# LT3045_and_LT3094.net
KiCad netlist of a schematic drawn in Altium Designer
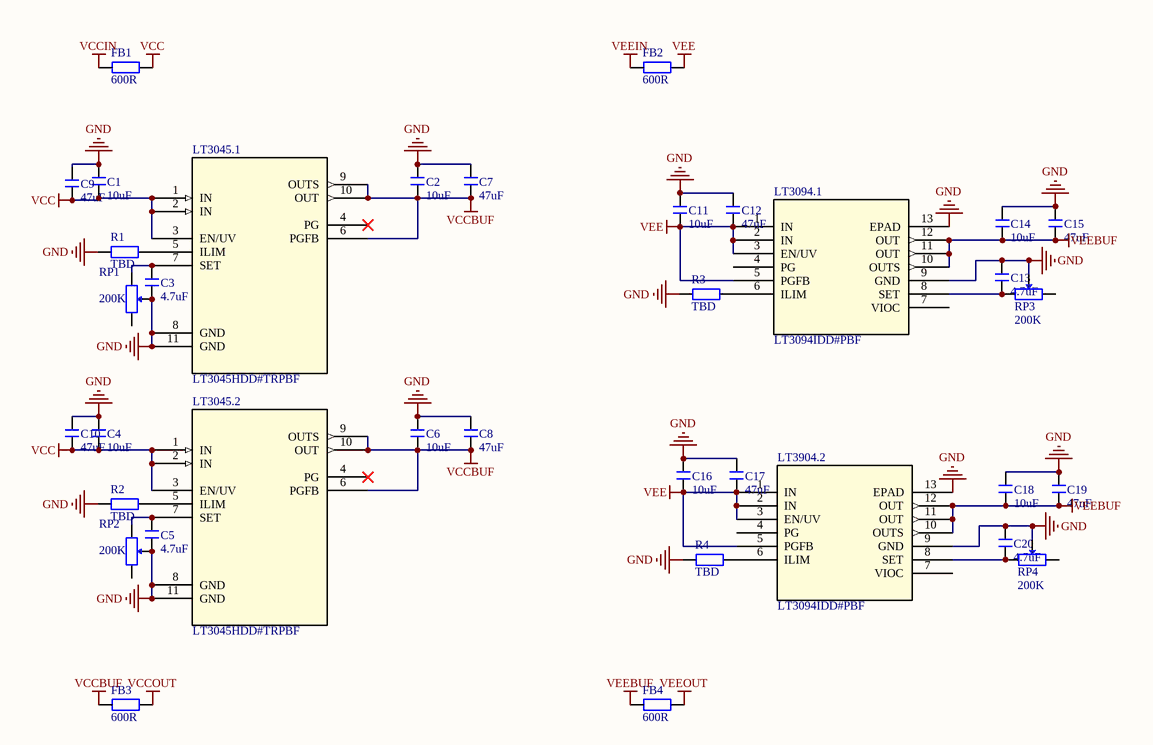
[diagram p0: LT3045 and LT3094.SchDoc]

(export (version "E")
  (design (tool "Eeschema 10.0.6"))
  (components
    (comp (ref "C1")
      (value "10uF")
      (footprint "C 0603_L")
      (description "无极性贴片电容")
      (fields (field (name "版权归属") "源创客"))
      (libsource (lib "IL") (part "C"))
    )
    (comp (ref "C2")
      (value "10uF")
      (footprint "C 0603_L")
      (description "无极性贴片电容")
      (fields (field (name "版权归属") "源创客"))
      (libsource (lib "IL") (part "C"))
    )
    (comp (ref "C3")
      (value "4.7uF")
      (footprint "C 0603_L")
      (description "无极性贴片电容")
      (fields (field (name "版权归属") "源创客"))
      (libsource (lib "IL") (part "C"))
    )
    (comp (ref "C4")
      (value "10uF")
      (footprint "C 0603_L")
      (description "无极性贴片电容")
      (fields (field (name "版权归属") "源创客"))
      (libsource (lib "IL") (part "C"))
    )
    (comp (ref "C5")
      (value "4.7uF")
      (footprint "C 0603_L")
      (description "无极性贴片电容")
      (fields (field (name "版权归属") "源创客"))
      (libsource (lib "IL") (part "C"))
    )
    (comp (ref "C6")
      (value "10uF")
      (footprint "C 0603_L")
      (description "无极性贴片电容")
      (fields (field (name "版权归属") "源创客"))
      (libsource (lib "IL") (part "C"))
    )
    (comp (ref "C7")
      (value "47uF")
      (footprint "C 0603_L")
      (description "无极性贴片电容")
      (fields (field (name "版权归属") "源创客"))
      (libsource (lib "IL") (part "C"))
    )
    (comp (ref "C8")
      (value "47uF")
      (footprint "C 0603_L")
      (description "无极性贴片电容")
      (fields (field (name "版权归属") "源创客"))
      (libsource (lib "IL") (part "C"))
    )
    (comp (ref "C9")
      (value "47uF")
      (footprint "C 0603_L")
      (description "无极性贴片电容")
      (fields (field (name "版权归属") "源创客"))
      (libsource (lib "IL") (part "C"))
    )
    (comp (ref "C10")
      (value "47uF")
      (footprint "C 0603_L")
      (description "无极性贴片电容")
      (fields (field (name "版权归属") "源创客"))
      (libsource (lib "IL") (part "C"))
    )
    (comp (ref "C11")
      (value "10uF")
      (footprint "C 0603_L")
      (description "无极性贴片电容")
      (fields (field (name "版权归属") "源创客"))
      (libsource (lib "IL") (part "C"))
    )
    (comp (ref "C12")
      (value "47uF")
      (footprint "C 0603_L")
      (description "无极性贴片电容")
      (fields (field (name "版权归属") "源创客"))
      (libsource (lib "IL") (part "C"))
    )
    (comp (ref "C13")
      (value "4.7uF")
      (footprint "C 0603_L")
      (description "无极性贴片电容")
      (fields (field (name "版权归属") "源创客"))
      (libsource (lib "IL") (part "C"))
    )
    (comp (ref "C14")
      (value "10uF")
      (footprint "C 0603_L")
      (description "无极性贴片电容")
      (fields (field (name "版权归属") "源创客"))
      (libsource (lib "IL") (part "C"))
    )
    (comp (ref "C15")
      (value "47uF")
      (footprint "C 0603_L")
      (description "无极性贴片电容")
      (fields (field (name "版权归属") "源创客"))
      (libsource (lib "IL") (part "C"))
    )
    (comp (ref "C16")
      (value "10uF")
      (footprint "C 0603_L")
      (description "无极性贴片电容")
      (fields (field (name "版权归属") "源创客"))
      (libsource (lib "IL") (part "C"))
    )
    (comp (ref "C17")
      (value "47uF")
      (footprint "C 0603_L")
      (description "无极性贴片电容")
      (fields (field (name "版权归属") "源创客"))
      (libsource (lib "IL") (part "C"))
    )
    (comp (ref "C18")
      (value "10uF")
      (footprint "C 0603_L")
      (description "无极性贴片电容")
      (fields (field (name "版权归属") "源创客"))
      (libsource (lib "IL") (part "C"))
    )
    (comp (ref "C19")
      (value "47uF")
      (footprint "C 0603_L")
      (description "无极性贴片电容")
      (fields (field (name "版权归属") "源创客"))
      (libsource (lib "IL") (part "C"))
    )
    (comp (ref "C20")
      (value "4.7uF")
      (footprint "C 0603_L")
      (description "无极性贴片电容")
      (fields (field (name "版权归属") "源创客"))
      (libsource (lib "IL") (part "C"))
    )
    (comp (ref "FB1") (value "600R") (footprint "FB-0805") (libsource (lib "Library") (part "FB")))
    (comp (ref "FB2") (value "600R") (footprint "FB-0805") (libsource (lib "Library") (part "FB")))
    (comp (ref "FB3") (value "600R") (footprint "FB-0805") (libsource (lib "Library") (part "FB")))
    (comp (ref "FB4") (value "600R") (footprint "FB-0805") (libsource (lib "Library") (part "FB")))
    (comp (ref "LT3045.1")
      (value "LT3045HDD#TRPBF")
      (footprint "other:DD_10_ADI-M")
      (description "No Description Available")
      (fields (field (name "COPYRIGHT") "Copyright (C) 2016 Accelerated Designs. All rights reserved"))
      (libsource (lib "IL") (part "LT3045HDD#TRPBF"))
    )
    (comp (ref "LT3045.2")
      (value "LT3045HDD#TRPBF")
      (footprint "other:DD_10_ADI-M")
      (description "No Description Available")
      (fields (field (name "COPYRIGHT") "Copyright (C) 2016 Accelerated Designs. All rights reserved"))
      (libsource (lib "IL") (part "LT3045HDD#TRPBF"))
    )
    (comp (ref "LT3094.1")
      (value "LT3094IDD#PBF")
      (footprint "other:DFN_12_ADI-L")
      (description "No Description Available")
      (fields (field (name "COPYRIGHT") "Copyright (C) 2018 Accelerated Designs. All rights reserved"))
      (libsource (lib "IL") (part "LT3094IDD#PBF"))
    )
    (comp (ref "LT3904.2")
      (value "LT3094IDD#PBF")
      (footprint "other:DFN_12_ADI-L")
      (description "No Description Available")
      (fields (field (name "COPYRIGHT") "Copyright (C) 2018 Accelerated Designs. All rights reserved"))
      (libsource (lib "IL") (part "LT3094IDD#PBF"))
    )
    (comp (ref "R1")
      (value "TBD")
      (footprint "R 0603_L")
      (description "贴片电阻")
      (fields (field (name "版权归属") "源创客"))
      (libsource (lib "IL") (part "R"))
    )
    (comp (ref "R2")
      (value "TBD")
      (footprint "R 0603_L")
      (description "贴片电阻")
      (fields (field (name "版权归属") "源创客"))
      (libsource (lib "IL") (part "R"))
    )
    (comp (ref "R3")
      (value "TBD")
      (footprint "R 0603_L")
      (description "贴片电阻")
      (fields (field (name "版权归属") "源创客"))
      (libsource (lib "IL") (part "R"))
    )
    (comp (ref "R4")
      (value "TBD")
      (footprint "R 0603_L")
      (description "贴片电阻")
      (fields (field (name "版权归属") "源创客"))
      (libsource (lib "IL") (part "R"))
    )
    (comp (ref "RP1")
      (value "200K")
      (footprint "3296W")
      (description "插件单联电位器")
      (fields (field (name "版权归属") "源创客"))
      (libsource (lib "IL") (part "RP-ID"))
    )
    (comp (ref "RP2")
      (value "200K")
      (footprint "3296W")
      (description "插件单联电位器")
      (fields (field (name "版权归属") "源创客"))
      (libsource (lib "IL") (part "RP-ID"))
    )
    (comp (ref "RP3")
      (value "200K")
      (footprint "3296W")
      (description "插件单联电位器")
      (fields (field (name "版权归属") "源创客"))
      (libsource (lib "IL") (part "RP-ID"))
    )
    (comp (ref "RP4")
      (value "200K")
      (footprint "3296W")
      (description "插件单联电位器")
      (fields (field (name "版权归属") "源创客"))
      (libsource (lib "IL") (part "RP-ID"))
    )
  )
  (nets
    (net (code "1") (name "GND") (class "Default")
      (node (ref "C1") (pin "2") (pinfunction "2_2") (pintype "passive"))
      (node (ref "C10") (pin "2") (pinfunction "2_2") (pintype "passive"))
      (node (ref "C11") (pin "2") (pinfunction "2_2") (pintype "passive"))
      (node (ref "C12") (pin "2") (pinfunction "2_2") (pintype "passive"))
      (node (ref "C13") (pin "1") (pinfunction "1_1") (pintype "passive"))
      (node (ref "C14") (pin "2") (pinfunction "2_2") (pintype "passive"))
      (node (ref "C15") (pin "2") (pinfunction "2_2") (pintype "passive"))
      (node (ref "C16") (pin "2") (pinfunction "2_2") (pintype "passive"))
      (node (ref "C17") (pin "2") (pinfunction "2_2") (pintype "passive"))
      (node (ref "C18") (pin "2") (pinfunction "2_2") (pintype "passive"))
      (node (ref "C19") (pin "2") (pinfunction "2_2") (pintype "passive"))
      (node (ref "C2") (pin "2") (pinfunction "2_2") (pintype "passive"))
      (node (ref "C20") (pin "1") (pinfunction "1_1") (pintype "passive"))
      (node (ref "C3") (pin "1") (pinfunction "1_1") (pintype "passive"))
      (node (ref "C4") (pin "2") (pinfunction "2_2") (pintype "passive"))
      (node (ref "C5") (pin "1") (pinfunction "1_1") (pintype "passive"))
      (node (ref "C6") (pin "2") (pinfunction "2_2") (pintype "passive"))
      (node (ref "C7") (pin "2") (pinfunction "2_2") (pintype "passive"))
      (node (ref "C8") (pin "2") (pinfunction "2_2") (pintype "passive"))
      (node (ref "C9") (pin "2") (pinfunction "2_2") (pintype "passive"))
      (node (ref "LT3045.1") (pin "11") (pinfunction "GND_11") (pintype "power_in"))
      (node (ref "LT3045.1") (pin "8") (pinfunction "GND_8") (pintype "power_in"))
      (node (ref "LT3045.2") (pin "11") (pinfunction "GND_11") (pintype "power_in"))
      (node (ref "LT3045.2") (pin "8") (pinfunction "GND_8") (pintype "power_in"))
      (node (ref "LT3094.1") (pin "13") (pinfunction "EPAD_13") (pintype "passive"))
      (node (ref "LT3094.1") (pin "9") (pinfunction "GND_9") (pintype "passive"))
      (node (ref "LT3904.2") (pin "13") (pinfunction "EPAD_13") (pintype "passive"))
      (node (ref "LT3904.2") (pin "9") (pinfunction "GND_9") (pintype "passive"))
      (node (ref "R1") (pin "1") (pinfunction "1_1") (pintype "passive"))
      (node (ref "R2") (pin "1") (pinfunction "1_1") (pintype "passive"))
      (node (ref "R3") (pin "1") (pinfunction "1_1") (pintype "passive"))
      (node (ref "R4") (pin "1") (pinfunction "1_1") (pintype "passive"))
      (node (ref "RP1") (pin "2") (pinfunction "2_2") (pintype "passive"))
      (node (ref "RP2") (pin "2") (pinfunction "2_2") (pintype "passive"))
      (node (ref "RP3") (pin "2") (pinfunction "2_2") (pintype "passive"))
      (node (ref "RP4") (pin "2") (pinfunction "2_2") (pintype "passive"))
    )
    (net (code "2") (name "Net-(LT3045.1-ILIM)") (class "Default")
      (node (ref "LT3045.1") (pin "5") (pinfunction "ILIM_5") (pintype "passive"))
      (node (ref "R1") (pin "2") (pinfunction "2_2") (pintype "passive"))
    )
    (net (code "3") (name "Net-(LT3045.1-SET)") (class "Default")
      (node (ref "C3") (pin "2") (pinfunction "2_2") (pintype "passive"))
      (node (ref "LT3045.1") (pin "7") (pinfunction "SET_7") (pintype "passive"))
      (node (ref "RP1") (pin "1") (pinfunction "1_1") (pintype "passive"))
    )
    (net (code "4") (name "Net-(LT3045.2-ILIM)") (class "Default")
      (node (ref "LT3045.2") (pin "5") (pinfunction "ILIM_5") (pintype "passive"))
      (node (ref "R2") (pin "2") (pinfunction "2_2") (pintype "passive"))
    )
    (net (code "5") (name "Net-(LT3045.2-SET)") (class "Default")
      (node (ref "C5") (pin "2") (pinfunction "2_2") (pintype "passive"))
      (node (ref "LT3045.2") (pin "7") (pinfunction "SET_7") (pintype "passive"))
      (node (ref "RP2") (pin "1") (pinfunction "1_1") (pintype "passive"))
    )
    (net (code "6") (name "Net-(LT3094.1-ILIM)") (class "Default")
      (node (ref "LT3094.1") (pin "6") (pinfunction "ILIM_6") (pintype "passive"))
      (node (ref "R3") (pin "2") (pinfunction "2_2") (pintype "passive"))
    )
    (net (code "7") (name "Net-(LT3094.1-SET)") (class "Default")
      (node (ref "C13") (pin "2") (pinfunction "2_2") (pintype "passive"))
      (node (ref "LT3094.1") (pin "8") (pinfunction "SET_8") (pintype "passive"))
      (node (ref "RP3") (pin "1") (pinfunction "1_1") (pintype "passive"))
    )
    (net (code "8") (name "Net-(LT3904.2-ILIM)") (class "Default")
      (node (ref "LT3904.2") (pin "6") (pinfunction "ILIM_6") (pintype "passive"))
      (node (ref "R4") (pin "2") (pinfunction "2_2") (pintype "passive"))
    )
    (net (code "9") (name "Net-(LT3904.2-SET)") (class "Default")
      (node (ref "C20") (pin "2") (pinfunction "2_2") (pintype "passive"))
      (node (ref "LT3904.2") (pin "8") (pinfunction "SET_8") (pintype "passive"))
      (node (ref "RP4") (pin "1") (pinfunction "1_1") (pintype "passive"))
    )
    (net (code "10") (name "VCC") (class "Default")
      (node (ref "C1") (pin "1") (pinfunction "1_1") (pintype "passive"))
      (node (ref "C10") (pin "1") (pinfunction "1_1") (pintype "passive"))
      (node (ref "C4") (pin "1") (pinfunction "1_1") (pintype "passive"))
      (node (ref "C9") (pin "1") (pinfunction "1_1") (pintype "passive"))
      (node (ref "FB1") (pin "2") (pinfunction "2_2") (pintype "passive"))
      (node (ref "LT3045.1") (pin "1") (pinfunction "IN_1") (pintype "input"))
      (node (ref "LT3045.1") (pin "2") (pinfunction "IN_2") (pintype "input"))
      (node (ref "LT3045.1") (pin "3") (pinfunction "EN/UV_3") (pintype "passive"))
      (node (ref "LT3045.2") (pin "1") (pinfunction "IN_1") (pintype "input"))
      (node (ref "LT3045.2") (pin "2") (pinfunction "IN_2") (pintype "input"))
      (node (ref "LT3045.2") (pin "3") (pinfunction "EN/UV_3") (pintype "passive"))
    )
    (net (code "11") (name "VCCBUF") (class "Default")
      (node (ref "C2") (pin "1") (pinfunction "1_1") (pintype "passive"))
      (node (ref "C6") (pin "1") (pinfunction "1_1") (pintype "passive"))
      (node (ref "C7") (pin "1") (pinfunction "1_1") (pintype "passive"))
      (node (ref "C8") (pin "1") (pinfunction "1_1") (pintype "passive"))
      (node (ref "FB3") (pin "1") (pinfunction "1_1") (pintype "passive"))
      (node (ref "LT3045.1") (pin "10") (pinfunction "OUT_10") (pintype "output"))
      (node (ref "LT3045.1") (pin "6") (pinfunction "PGFB_6") (pintype "passive"))
      (node (ref "LT3045.1") (pin "9") (pinfunction "OUTS_9") (pintype "output"))
      (node (ref "LT3045.2") (pin "10") (pinfunction "OUT_10") (pintype "output"))
      (node (ref "LT3045.2") (pin "6") (pinfunction "PGFB_6") (pintype "passive"))
      (node (ref "LT3045.2") (pin "9") (pinfunction "OUTS_9") (pintype "output"))
    )
    (net (code "12") (name "VCCIN") (class "Default")
      (node (ref "FB1") (pin "1") (pinfunction "1_1") (pintype "passive"))
    )
    (net (code "13") (name "VCCOUT") (class "Default")
      (node (ref "FB3") (pin "2") (pinfunction "2_2") (pintype "passive"))
    )
    (net (code "14") (name "VEE") (class "Default")
      (node (ref "C11") (pin "1") (pinfunction "1_1") (pintype "passive"))
      (node (ref "C12") (pin "1") (pinfunction "1_1") (pintype "passive"))
      (node (ref "C16") (pin "1") (pinfunction "1_1") (pintype "passive"))
      (node (ref "C17") (pin "1") (pinfunction "1_1") (pintype "passive"))
      (node (ref "FB2") (pin "2") (pinfunction "2_2") (pintype "passive"))
      (node (ref "LT3094.1") (pin "1") (pinfunction "IN_1") (pintype "passive"))
      (node (ref "LT3094.1") (pin "2") (pinfunction "IN_2") (pintype "passive"))
      (node (ref "LT3094.1") (pin "3") (pinfunction "EN/UV_3") (pintype "passive"))
      (node (ref "LT3094.1") (pin "5") (pinfunction "PGFB_5") (pintype "passive"))
      (node (ref "LT3904.2") (pin "1") (pinfunction "IN_1") (pintype "passive"))
      (node (ref "LT3904.2") (pin "2") (pinfunction "IN_2") (pintype "passive"))
      (node (ref "LT3904.2") (pin "3") (pinfunction "EN/UV_3") (pintype "passive"))
      (node (ref "LT3904.2") (pin "5") (pinfunction "PGFB_5") (pintype "passive"))
    )
    (net (code "15") (name "VEEBUF") (class "Default")
      (node (ref "C14") (pin "1") (pinfunction "1_1") (pintype "passive"))
      (node (ref "C15") (pin "1") (pinfunction "1_1") (pintype "passive"))
      (node (ref "C18") (pin "1") (pinfunction "1_1") (pintype "passive"))
      (node (ref "C19") (pin "1") (pinfunction "1_1") (pintype "passive"))
      (node (ref "FB4") (pin "1") (pinfunction "1_1") (pintype "passive"))
      (node (ref "LT3094.1") (pin "10") (pinfunction "OUTS_10") (pintype "output"))
      (node (ref "LT3094.1") (pin "11") (pinfunction "OUT_11") (pintype "output"))
      (node (ref "LT3094.1") (pin "12") (pinfunction "OUT_12") (pintype "output"))
      (node (ref "LT3904.2") (pin "10") (pinfunction "OUTS_10") (pintype "output"))
      (node (ref "LT3904.2") (pin "11") (pinfunction "OUT_11") (pintype "output"))
      (node (ref "LT3904.2") (pin "12") (pinfunction "OUT_12") (pintype "output"))
    )
    (net (code "16") (name "VEEIN") (class "Default")
      (node (ref "FB2") (pin "1") (pinfunction "1_1") (pintype "passive"))
    )
    (net (code "17") (name "VEEOUT") (class "Default")
      (node (ref "FB4") (pin "2") (pinfunction "2_2") (pintype "passive"))
    )
    (net (code "18") (name "unconnected-(LT3045.1-PG-Pad4)") (class "Default")
      (node (ref "LT3045.1") (pin "4") (pinfunction "PG_4") (pintype "passive+no_connect"))
    )
    (net (code "19") (name "unconnected-(LT3045.2-PG-Pad4)") (class "Default")
      (node (ref "LT3045.2") (pin "4") (pinfunction "PG_4") (pintype "passive+no_connect"))
    )
    (net (code "20") (name "unconnected-(LT3094.1-PG-Pad4)") (class "Default")
      (node (ref "LT3094.1") (pin "4") (pinfunction "PG_4") (pintype "passive"))
    )
    (net (code "21") (name "unconnected-(LT3094.1-VIOC-Pad7)") (class "Default")
      (node (ref "LT3094.1") (pin "7") (pinfunction "VIOC_7") (pintype "passive"))
    )
    (net (code "22") (name "unconnected-(LT3904.2-PG-Pad4)") (class "Default")
      (node (ref "LT3904.2") (pin "4") (pinfunction "PG_4") (pintype "passive"))
    )
    (net (code "23") (name "unconnected-(LT3904.2-VIOC-Pad7)") (class "Default")
      (node (ref "LT3904.2") (pin "7") (pinfunction "VIOC_7") (pintype "passive"))
    )
    (net (code "24") (name "unconnected-(RP1-Pad3)") (class "Default")
      (node (ref "RP1") (pin "3") (pinfunction "3_3") (pintype "passive"))
    )
    (net (code "25") (name "unconnected-(RP2-Pad3)") (class "Default")
      (node (ref "RP2") (pin "3") (pinfunction "3_3") (pintype "passive"))
    )
    (net (code "26") (name "unconnected-(RP3-Pad3)") (class "Default")
      (node (ref "RP3") (pin "3") (pinfunction "3_3") (pintype "passive"))
    )
    (net (code "27") (name "unconnected-(RP4-Pad3)") (class "Default")
      (node (ref "RP4") (pin "3") (pinfunction "3_3") (pintype "passive"))
    )
  )
)
